# quick-907.net
KiCad netlist of a schematic drawn in Altium Designer
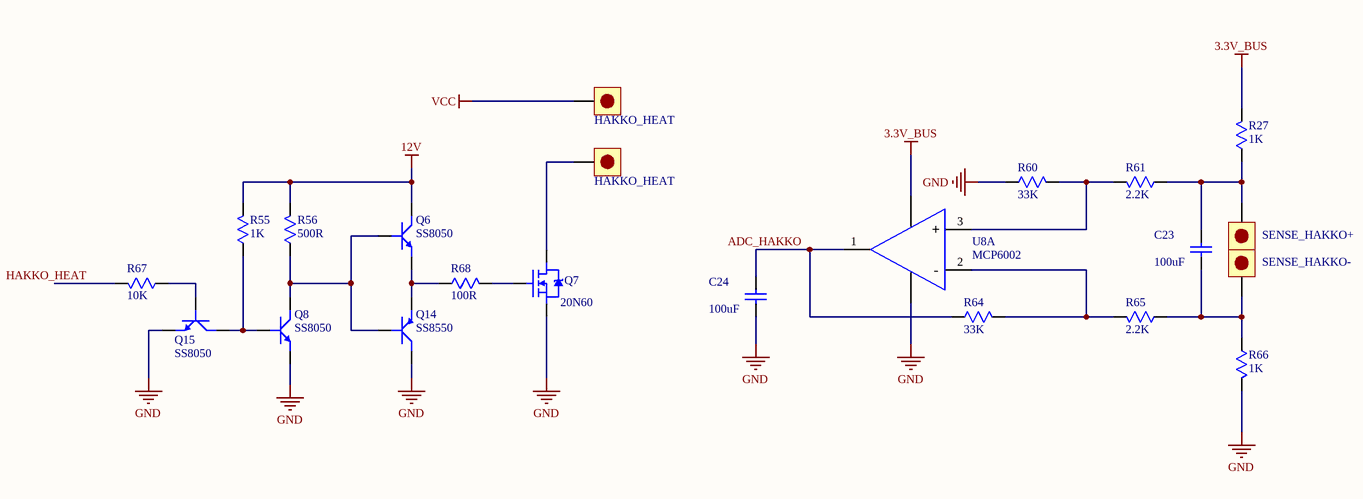
[diagram p0: quick-907.SchDoc]

(export (version "E")
  (design (tool "Eeschema 10.0.6"))
  (components
    (comp (ref "C23")
      (value "100uF")
      (footprint "C0805")
      (libsource (lib "Huan_basic") (part "Capacitor_non-polar"))
    )
    (comp (ref "C24")
      (value "100uF")
      (footprint "C0805")
      (libsource (lib "Huan_basic") (part "Capacitor_non-polar"))
    )
    (comp (ref "PAD8")
      (value "SENSE_HAKKO-")
      (footprint "THROUGH_HOLE_MEDIUM")
      (libsource (lib "Huan_basic") (part "Pad_Through_Hole"))
    )
    (comp (ref "PAD9")
      (value "SENSE_HAKKO+")
      (footprint "THROUGH_HOLE_MEDIUM")
      (libsource (lib "") (part "Pad_Through_Hole_2"))
    )
    (comp (ref "PAD15")
      (value "HAKKO_HEAT")
      (footprint "THROUGH_HOLE_MEDIUM")
      (libsource (lib "") (part "Pad_Through_Hole_1"))
    )
    (comp (ref "PAD16")
      (value "HAKKO_HEAT")
      (footprint "THROUGH_HOLE_MEDIUM")
      (libsource (lib "") (part "Pad_Through_Hole_1"))
    )
    (comp (ref "Q6")
      (value "SS8050")
      (footprint "SOT-23")
      (libsource (lib "Huan_basic") (part "Transistor-NPN"))
    )
    (comp (ref "Q7")
      (value "20N60")
      (footprint "TO-252-2")
      (libsource (lib "Huan_basic") (part "MOSFET_N-Chanel"))
    )
    (comp (ref "Q8")
      (value "SS8050")
      (footprint "SOT-23")
      (libsource (lib "Huan_basic") (part "Transistor-NPN"))
    )
    (comp (ref "Q14")
      (value "SS8550")
      (footprint "SOT-23")
      (libsource (lib "Huan_basic") (part "Transistor-PNP"))
    )
    (comp (ref "Q15")
      (value "SS8050")
      (footprint "SOT-23")
      (libsource (lib "Huan_basic") (part "Transistor-NPN"))
    )
    (comp (ref "R27") (value "1K") (footprint "R0805") (libsource (lib "Huan_basic") (part "Resistor")))
    (comp (ref "R55") (value "1K") (footprint "R0805") (libsource (lib "Huan_basic") (part "Resistor")))
    (comp (ref "R56") (value "500R") (footprint "R0805") (libsource (lib "Huan_basic") (part "Resistor")))
    (comp (ref "R60") (value "33K") (footprint "R0805") (libsource (lib "Huan_basic") (part "Resistor")))
    (comp (ref "R61") (value "2.2K") (footprint "R0805") (libsource (lib "Huan_basic") (part "Resistor")))
    (comp (ref "R64") (value "33K") (footprint "R0805") (libsource (lib "Huan_basic") (part "Resistor")))
    (comp (ref "R65") (value "2.2K") (footprint "R0805") (libsource (lib "Huan_basic") (part "Resistor")))
    (comp (ref "R66") (value "1K") (footprint "R0805") (libsource (lib "Huan_basic") (part "Resistor")))
    (comp (ref "R67") (value "10K") (footprint "R0805") (libsource (lib "Huan_basic") (part "Resistor")))
    (comp (ref "R68") (value "100R") (footprint "R0805") (libsource (lib "Huan_basic") (part "Resistor")))
    (comp (ref "U8")
      (value "MCP6002")
      (footprint "DIP-8")
      (libsource (lib "Huan_basic") (part "Op-Amply/Comparator"))
    )
  )
  (nets
    (net (code "1") (name "/ADC_HAKKO") (class "Default")
      (node (ref "C24") (pin "1") (pinfunction "1_1") (pintype "passive"))
      (node (ref "R64") (pin "1") (pinfunction "1_1") (pintype "passive"))
      (node (ref "U8") (pin "1") (pinfunction "1_1") (pintype "passive"))
    )
    (net (code "2") (name "/HAKKO_HEAT") (class "Default")
      (node (ref "R67") (pin "1") (pinfunction "1_1") (pintype "passive"))
    )
    (net (code "3") (name "3.3V_BUS") (class "Default")
      (node (ref "R27") (pin "2") (pinfunction "2_2") (pintype "passive"))
      (node (ref "U8") (pin "8") (pinfunction "8_8") (pintype "passive"))
    )
    (net (code "4") (name "12V") (class "Default")
      (node (ref "Q6") (pin "3") (pinfunction "C_3") (pintype "passive"))
      (node (ref "R55") (pin "1") (pinfunction "1_1") (pintype "passive"))
      (node (ref "R56") (pin "1") (pinfunction "1_1") (pintype "passive"))
    )
    (net (code "5") (name "GND") (class "Default")
      (node (ref "C24") (pin "2") (pinfunction "2_2") (pintype "passive"))
      (node (ref "Q14") (pin "3") (pinfunction "C_3") (pintype "passive"))
      (node (ref "Q15") (pin "2") (pinfunction "E_2") (pintype "passive"))
      (node (ref "Q7") (pin "3") (pinfunction "S_3") (pintype "passive"))
      (node (ref "Q8") (pin "2") (pinfunction "E_2") (pintype "passive"))
      (node (ref "R60") (pin "1") (pinfunction "1_1") (pintype "passive"))
      (node (ref "R66") (pin "2") (pinfunction "2_2") (pintype "passive"))
      (node (ref "U8") (pin "4") (pinfunction "4_4") (pintype "passive"))
    )
    (net (code "6") (name "Net-(C23-Pad1)") (class "Default")
      (node (ref "C23") (pin "1") (pinfunction "1_1") (pintype "passive"))
      (node (ref "PAD9") (pin "1") (pintype "passive"))
      (node (ref "R27") (pin "1") (pinfunction "1_1") (pintype "passive"))
      (node (ref "R61") (pin "1") (pinfunction "1_1") (pintype "passive"))
    )
    (net (code "7") (name "Net-(C23-Pad2)") (class "Default")
      (node (ref "C23") (pin "2") (pinfunction "2_2") (pintype "passive"))
      (node (ref "PAD8") (pin "1") (pintype "passive"))
      (node (ref "R65") (pin "1") (pinfunction "1_1") (pintype "passive"))
      (node (ref "R66") (pin "1") (pinfunction "1_1") (pintype "passive"))
    )
    (net (code "8") (name "Net-(Q7-D)") (class "Default")
      (node (ref "PAD16") (pin "1") (pintype "passive"))
      (node (ref "Q7") (pin "2") (pinfunction "D_2") (pintype "passive"))
    )
    (net (code "9") (name "Net-(Q7-G)") (class "Default")
      (node (ref "Q7") (pin "1") (pinfunction "G_1") (pintype "passive"))
      (node (ref "R68") (pin "1") (pinfunction "1_1") (pintype "passive"))
    )
    (net (code "10") (name "Net-(Q14-B)") (class "Default")
      (node (ref "Q14") (pin "1") (pinfunction "B_1") (pintype "passive"))
      (node (ref "Q6") (pin "1") (pinfunction "B_1") (pintype "passive"))
      (node (ref "Q8") (pin "3") (pinfunction "C_3") (pintype "passive"))
      (node (ref "R56") (pin "2") (pinfunction "2_2") (pintype "passive"))
    )
    (net (code "11") (name "Net-(Q14-E)") (class "Default")
      (node (ref "Q14") (pin "2") (pinfunction "E_2") (pintype "passive"))
      (node (ref "Q6") (pin "2") (pinfunction "E_2") (pintype "passive"))
      (node (ref "R68") (pin "2") (pinfunction "2_2") (pintype "passive"))
    )
    (net (code "12") (name "Net-(Q15-B)") (class "Default")
      (node (ref "Q15") (pin "1") (pinfunction "B_1") (pintype "passive"))
      (node (ref "R67") (pin "2") (pinfunction "2_2") (pintype "passive"))
    )
    (net (code "13") (name "Net-(Q15-C)") (class "Default")
      (node (ref "Q15") (pin "3") (pinfunction "C_3") (pintype "passive"))
      (node (ref "Q8") (pin "1") (pinfunction "B_1") (pintype "passive"))
      (node (ref "R55") (pin "2") (pinfunction "2_2") (pintype "passive"))
    )
    (net (code "14") (name "Net-(U8A-+)") (class "Default")
      (node (ref "R60") (pin "2") (pinfunction "2_2") (pintype "passive"))
      (node (ref "R61") (pin "2") (pinfunction "2_2") (pintype "passive"))
      (node (ref "U8") (pin "3") (pinfunction "+_3") (pintype "passive"))
    )
    (net (code "15") (name "Net-(U8A--)") (class "Default")
      (node (ref "R64") (pin "2") (pinfunction "2_2") (pintype "passive"))
      (node (ref "R65") (pin "2") (pinfunction "2_2") (pintype "passive"))
      (node (ref "U8") (pin "2") (pinfunction "-_2") (pintype "passive"))
    )
    (net (code "16") (name "VCC") (class "Default") (node (ref "PAD15") (pin "1") (pintype "passive")))
  )
)
